# PCB.net
KiCad netlist of a schematic drawn in EasyEDA Pro
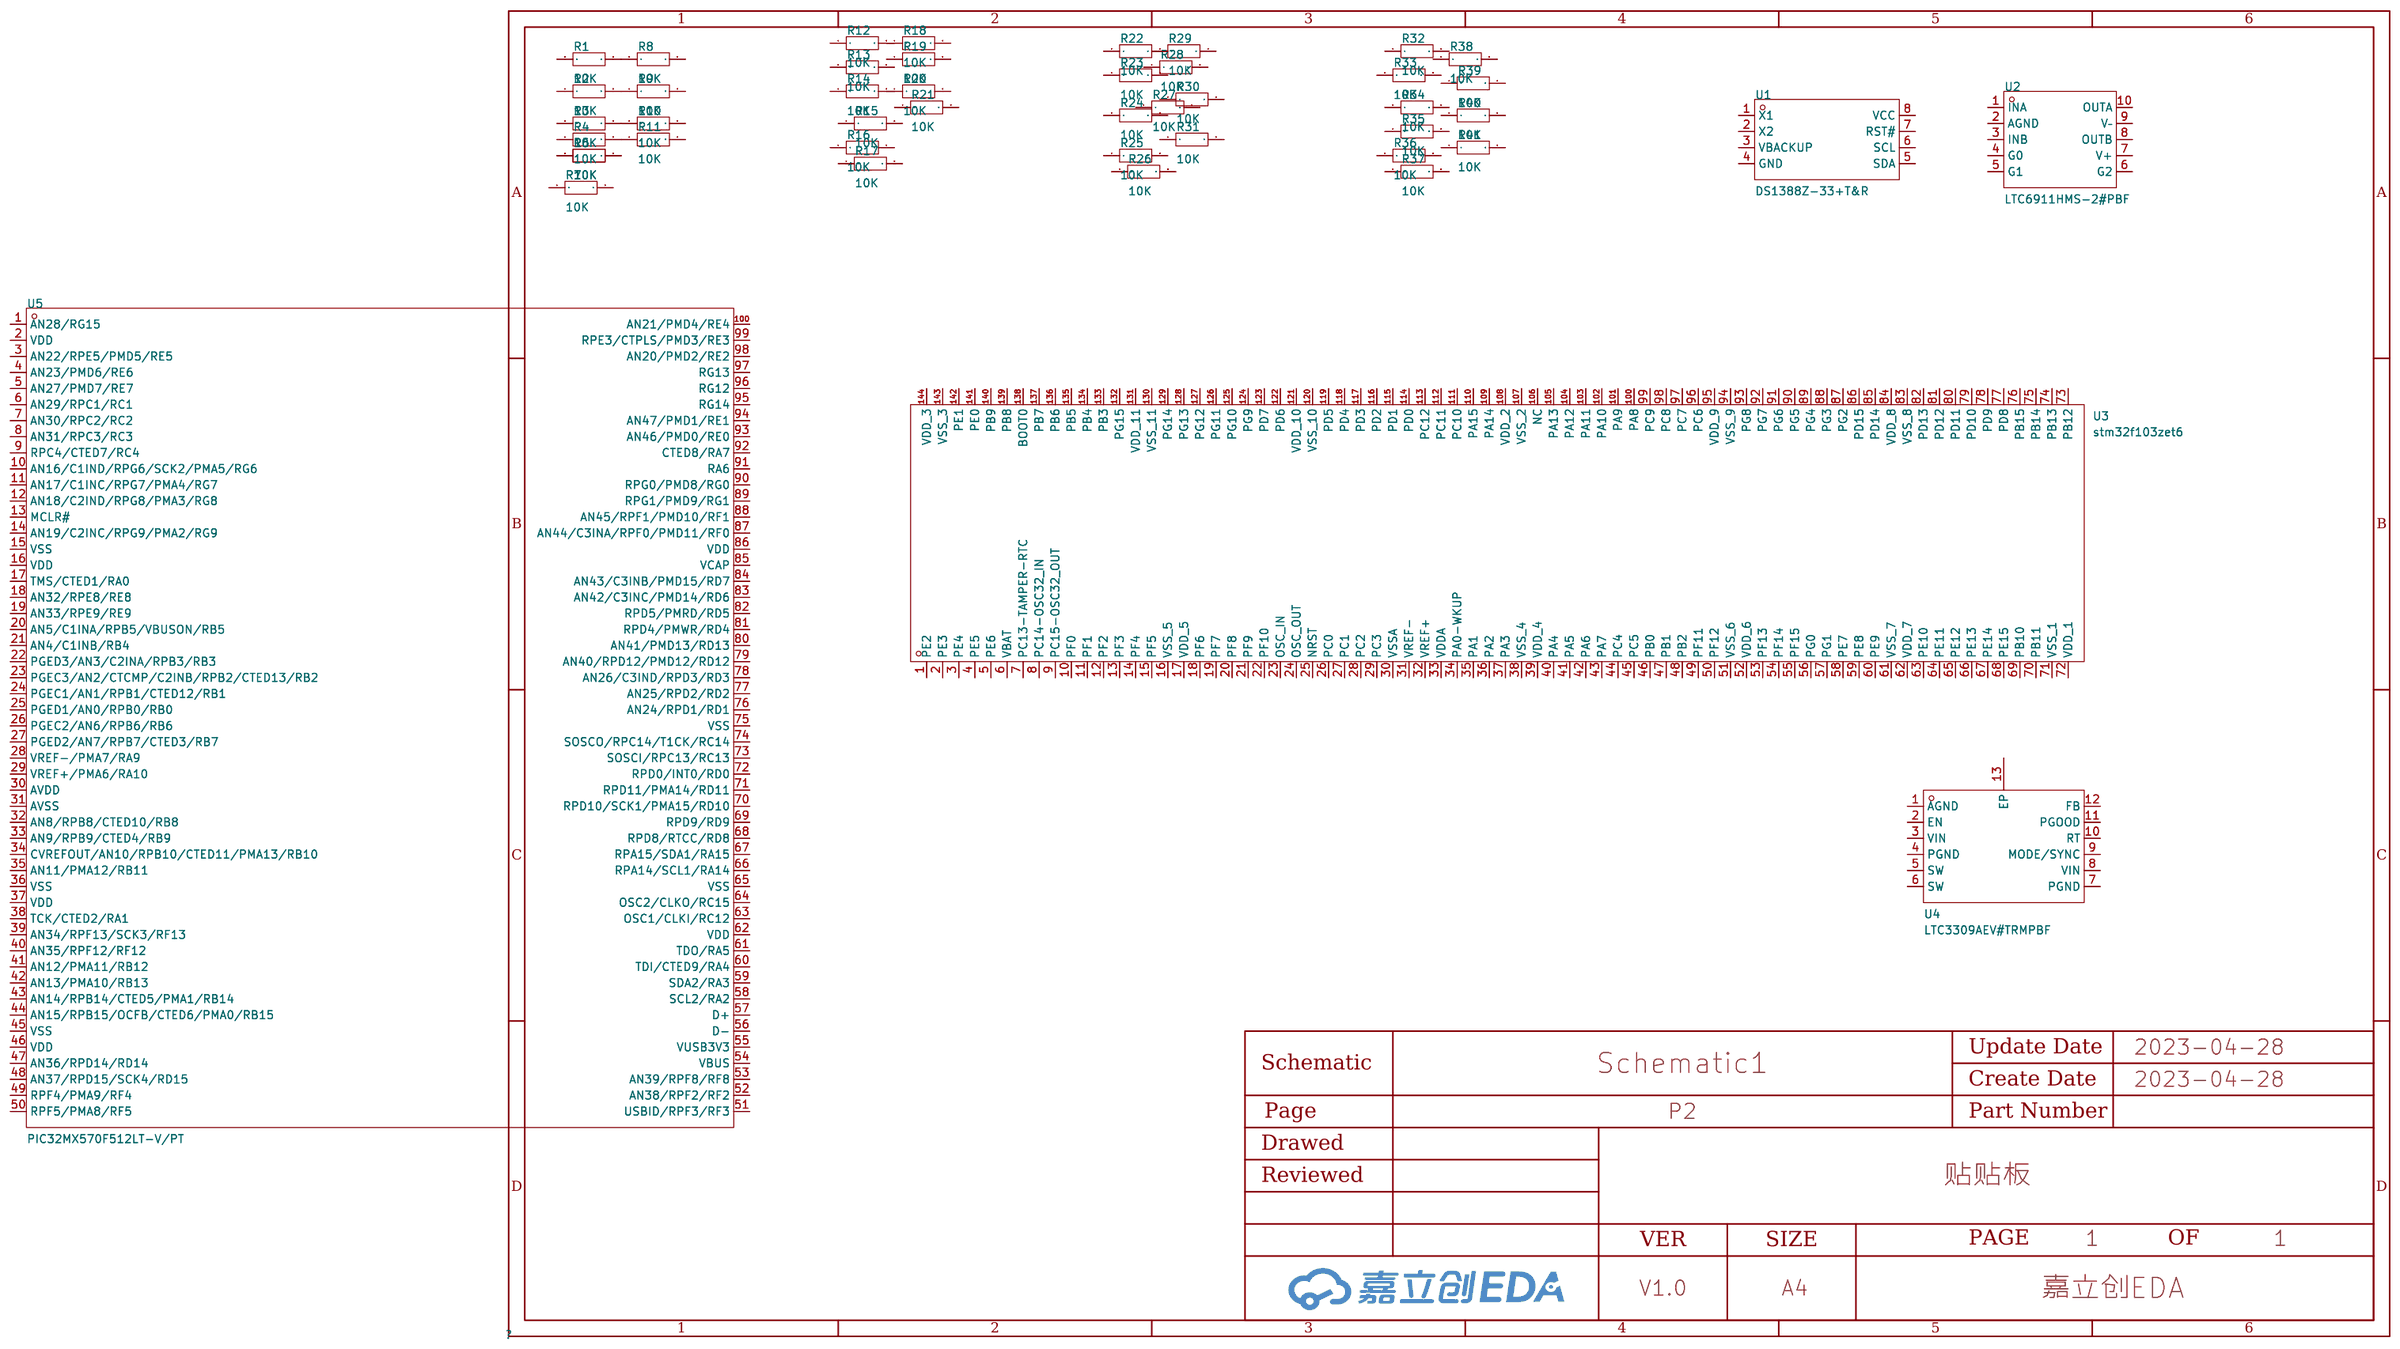
[diagram p0: schematic sheet]

(export (version "E")
  (design (tool "Eeschema 10.0.6"))
  (components
    (comp (ref "R1") (value "10K") (footprint "easyedapro:R1206") (libsource (lib "easyedapro") (part "电阻")))
    (comp (ref "R2") (value "10K") (footprint "easyedapro:R1206") (libsource (lib "easyedapro") (part "电阻")))
    (comp (ref "R3") (value "10K") (footprint "easyedapro:R1206") (libsource (lib "easyedapro") (part "电阻")))
    (comp (ref "R4") (value "10K") (footprint "easyedapro:R1206") (libsource (lib "easyedapro") (part "电阻")))
    (comp (ref "R5") (value "10K") (footprint "easyedapro:R1206") (libsource (lib "easyedapro") (part "电阻")))
    (comp (ref "R6") (value "10K") (footprint "easyedapro:R1206") (libsource (lib "easyedapro") (part "电阻")))
    (comp (ref "R7") (value "10K") (footprint "easyedapro:R1206") (libsource (lib "easyedapro") (part "电阻")))
    (comp (ref "R8") (value "10K") (footprint "easyedapro:R1206") (libsource (lib "easyedapro") (part "电阻")))
    (comp (ref "R9") (value "10K") (footprint "easyedapro:R1206") (libsource (lib "easyedapro") (part "电阻")))
    (comp (ref "R10") (value "10K") (footprint "easyedapro:R1206") (libsource (lib "easyedapro") (part "电阻")))
    (comp (ref "R11") (value "10K") (footprint "easyedapro:R1206") (libsource (lib "easyedapro") (part "电阻")))
    (comp (ref "R12") (value "10K") (footprint "easyedapro:R1206") (libsource (lib "easyedapro") (part "电阻")))
    (comp (ref "R13") (value "10K") (footprint "easyedapro:R1206") (libsource (lib "easyedapro") (part "电阻")))
    (comp (ref "R14") (value "10K") (footprint "easyedapro:R1206") (libsource (lib "easyedapro") (part "电阻")))
    (comp (ref "R15") (value "10K") (footprint "easyedapro:R1206") (libsource (lib "easyedapro") (part "电阻")))
    (comp (ref "R16") (value "10K") (footprint "easyedapro:R1206") (libsource (lib "easyedapro") (part "电阻")))
    (comp (ref "R17") (value "10K") (footprint "easyedapro:R1206") (libsource (lib "easyedapro") (part "电阻")))
    (comp (ref "R18") (value "10K") (footprint "easyedapro:R1206") (libsource (lib "easyedapro") (part "电阻")))
    (comp (ref "R19") (value "10K") (footprint "easyedapro:R1206") (libsource (lib "easyedapro") (part "电阻")))
    (comp (ref "R20") (value "10K") (footprint "easyedapro:R1206") (libsource (lib "easyedapro") (part "电阻")))
    (comp (ref "R21") (value "10K") (footprint "easyedapro:R1206") (libsource (lib "easyedapro") (part "电阻")))
    (comp (ref "R22") (value "10K") (footprint "easyedapro:R1206") (libsource (lib "easyedapro") (part "电阻")))
    (comp (ref "R23") (value "10K") (footprint "easyedapro:R1206") (libsource (lib "easyedapro") (part "电阻")))
    (comp (ref "R24") (value "10K") (footprint "easyedapro:R1206") (libsource (lib "easyedapro") (part "电阻")))
    (comp (ref "R25") (value "10K") (footprint "easyedapro:R1206") (libsource (lib "easyedapro") (part "电阻")))
    (comp (ref "R26") (value "10K") (footprint "easyedapro:R1206") (libsource (lib "easyedapro") (part "电阻")))
    (comp (ref "R27") (value "10K") (footprint "easyedapro:R1206") (libsource (lib "easyedapro") (part "电阻")))
    (comp (ref "R28") (value "10K") (footprint "easyedapro:R1206") (libsource (lib "easyedapro") (part "电阻")))
    (comp (ref "R29") (value "10K") (footprint "easyedapro:R1206") (libsource (lib "easyedapro") (part "电阻")))
    (comp (ref "R30") (value "10K") (footprint "easyedapro:R1206") (libsource (lib "easyedapro") (part "电阻")))
    (comp (ref "R31") (value "10K") (footprint "easyedapro:R1206") (libsource (lib "easyedapro") (part "电阻")))
    (comp (ref "R32") (value "10K") (footprint "easyedapro:R1206") (libsource (lib "easyedapro") (part "电阻")))
    (comp (ref "R33") (value "10K") (footprint "easyedapro:R1206") (libsource (lib "easyedapro") (part "电阻")))
    (comp (ref "R34") (value "10K") (footprint "easyedapro:R1206") (libsource (lib "easyedapro") (part "电阻")))
    (comp (ref "R35") (value "10K") (footprint "easyedapro:R1206") (libsource (lib "easyedapro") (part "电阻")))
    (comp (ref "R36") (value "10K") (footprint "easyedapro:R1206") (libsource (lib "easyedapro") (part "电阻")))
    (comp (ref "R37") (value "10K") (footprint "easyedapro:R1206") (libsource (lib "easyedapro") (part "电阻")))
    (comp (ref "R38") (value "10K") (footprint "easyedapro:R1206") (libsource (lib "easyedapro") (part "电阻")))
    (comp (ref "R39") (value "10K") (footprint "easyedapro:R1206") (libsource (lib "easyedapro") (part "电阻")))
    (comp (ref "R40") (value "10K") (footprint "easyedapro:R1206") (libsource (lib "easyedapro") (part "电阻")))
    (comp (ref "R41") (value "10K") (footprint "easyedapro:R1206") (libsource (lib "easyedapro") (part "电阻")))
    (comp (ref "U1")
      (value "DS1388Z-33+T&R")
      (footprint "easyedapro:SOIC-8_L4.9-W3.9-P1.27-LS6.0-BL")
      (description "接口:I2C;")
      (fields (field (name "Manufacturer") "ADI(亚德诺)/MAXIM(美信)"))
      (libsource (lib "easyedapro") (part "DS1388Z-33+T&R"))
    )
    (comp (ref "U2")
      (value "LTC6911HMS-2#PBF")
      (footprint "easyedapro:MSOP-10_L3.0-W3.0-P0.50-LS4.9-BL")
      (description "放大器类型:-;通道数:2;-3dB带宽:-;输入偏置电流(Ib):-;压摆率(SR):16V/us;")
      (fields (field (name "Manufacturer") "ADI(亚德诺)"))
      (libsource (lib "easyedapro") (part "LTC6911HMS-2#PBF"))
    )
    (comp (ref "U3")
      (value "stm32f103zet6")
      (footprint "easyedapro:LQFP-144_L20.0-W20.0-P0.50-LS22.0-BL")
      (libsource (lib "easyedapro") (part "STM32F103ZET6_C9900046927"))
    )
    (comp (ref "U4")
      (value "LTC3309AEV#TRMPBF")
      (footprint "easyedapro:LQFN-12_L2.0-W2.0-P0.50-TL-EP0.7")
      (fields (field (name "Manufacturer") "ADI(亚德诺)/LINEAR(凌特)"))
      (libsource (lib "easyedapro") (part "LTC3309AEV#TRMPBF"))
    )
    (comp (ref "U5")
      (value "PIC32MX570F512LT-V/PT")
      (footprint "easyedapro:TQFP-100_L12.0-W12.0-P0.40-LS14.0-BL")
      (fields (field (name "Manufacturer") "MICROCHIP(美国微芯)"))
      (libsource (lib "easyedapro") (part "PIC32MX570F512LT-V/PT"))
    )
  )
  (nets
    (net (code "1") (name "Net-(R1-Pad2)") (class "Default")
      (node (ref "R1") (pin "2") (pinfunction "2_2") (pintype "input"))
      (node (ref "R8") (pin "1") (pinfunction "1_1") (pintype "input"))
    )
    (net (code "2") (name "Net-(R2-Pad2)") (class "Default")
      (node (ref "R2") (pin "2") (pinfunction "2_2") (pintype "input"))
      (node (ref "R9") (pin "1") (pinfunction "1_1") (pintype "input"))
    )
    (net (code "3") (name "Net-(R5-Pad1)") (class "Default")
      (node (ref "R5") (pin "1") (pinfunction "1_1") (pintype "input"))
      (node (ref "R6") (pin "1") (pinfunction "1_1") (pintype "input"))
    )
    (net (code "4") (name "Net-(R5-Pad2)") (class "Default")
      (node (ref "R5") (pin "2") (pinfunction "2_2") (pintype "input"))
      (node (ref "R6") (pin "2") (pinfunction "2_2") (pintype "input"))
    )
    (net (code "5") (name "Net-(R10-Pad1)") (class "Default")
      (node (ref "R10") (pin "1") (pinfunction "1_1") (pintype "input"))
      (node (ref "R3") (pin "2") (pinfunction "2_2") (pintype "input"))
    )
    (net (code "6") (name "Net-(R11-Pad1)") (class "Default")
      (node (ref "R11") (pin "1") (pinfunction "1_1") (pintype "input"))
      (node (ref "R4") (pin "2") (pinfunction "2_2") (pintype "input"))
    )
    (net (code "7") (name "unconnected-(R1-Pad1)") (class "Default")
      (node (ref "R1") (pin "1") (pinfunction "1_1") (pintype "input"))
    )
    (net (code "8") (name "unconnected-(R2-Pad1)") (class "Default")
      (node (ref "R2") (pin "1") (pinfunction "1_1") (pintype "input"))
    )
    (net (code "9") (name "unconnected-(R3-Pad1)") (class "Default")
      (node (ref "R3") (pin "1") (pinfunction "1_1") (pintype "input"))
    )
    (net (code "10") (name "unconnected-(R4-Pad1)") (class "Default")
      (node (ref "R4") (pin "1") (pinfunction "1_1") (pintype "input"))
    )
    (net (code "11") (name "unconnected-(R7-Pad1)") (class "Default")
      (node (ref "R7") (pin "1") (pinfunction "1_1") (pintype "input"))
    )
    (net (code "12") (name "unconnected-(R7-Pad2)") (class "Default")
      (node (ref "R7") (pin "2") (pinfunction "2_2") (pintype "input"))
    )
    (net (code "13") (name "unconnected-(R8-Pad2)") (class "Default")
      (node (ref "R8") (pin "2") (pinfunction "2_2") (pintype "input"))
    )
    (net (code "14") (name "unconnected-(R9-Pad2)") (class "Default")
      (node (ref "R9") (pin "2") (pinfunction "2_2") (pintype "input"))
    )
    (net (code "15") (name "unconnected-(R10-Pad2)") (class "Default")
      (node (ref "R10") (pin "2") (pinfunction "2_2") (pintype "input"))
    )
    (net (code "16") (name "unconnected-(R11-Pad2)") (class "Default")
      (node (ref "R11") (pin "2") (pinfunction "2_2") (pintype "input"))
    )
    (net (code "17") (name "unconnected-(R12-Pad1)") (class "Default")
      (node (ref "R12") (pin "1") (pinfunction "1_1") (pintype "input"))
    )
    (net (code "18") (name "unconnected-(R12-Pad2)") (class "Default")
      (node (ref "R12") (pin "2") (pinfunction "2_2") (pintype "input"))
    )
    (net (code "19") (name "unconnected-(R13-Pad1)") (class "Default")
      (node (ref "R13") (pin "1") (pinfunction "1_1") (pintype "input"))
    )
    (net (code "20") (name "unconnected-(R13-Pad2)") (class "Default")
      (node (ref "R13") (pin "2") (pinfunction "2_2") (pintype "input"))
    )
    (net (code "21") (name "unconnected-(R14-Pad1)") (class "Default")
      (node (ref "R14") (pin "1") (pinfunction "1_1") (pintype "input"))
    )
    (net (code "22") (name "unconnected-(R14-Pad2)") (class "Default")
      (node (ref "R14") (pin "2") (pinfunction "2_2") (pintype "input"))
    )
    (net (code "23") (name "unconnected-(R15-Pad1)") (class "Default")
      (node (ref "R15") (pin "1") (pinfunction "1_1") (pintype "input"))
    )
    (net (code "24") (name "unconnected-(R15-Pad2)") (class "Default")
      (node (ref "R15") (pin "2") (pinfunction "2_2") (pintype "input"))
    )
    (net (code "25") (name "unconnected-(R16-Pad1)") (class "Default")
      (node (ref "R16") (pin "1") (pinfunction "1_1") (pintype "input"))
    )
    (net (code "26") (name "unconnected-(R16-Pad2)") (class "Default")
      (node (ref "R16") (pin "2") (pinfunction "2_2") (pintype "input"))
    )
    (net (code "27") (name "unconnected-(R17-Pad1)") (class "Default")
      (node (ref "R17") (pin "1") (pinfunction "1_1") (pintype "input"))
    )
    (net (code "28") (name "unconnected-(R17-Pad2)") (class "Default")
      (node (ref "R17") (pin "2") (pinfunction "2_2") (pintype "input"))
    )
    (net (code "29") (name "unconnected-(R18-Pad1)") (class "Default")
      (node (ref "R18") (pin "1") (pinfunction "1_1") (pintype "input"))
    )
    (net (code "30") (name "unconnected-(R18-Pad2)") (class "Default")
      (node (ref "R18") (pin "2") (pinfunction "2_2") (pintype "input"))
    )
    (net (code "31") (name "unconnected-(R19-Pad1)") (class "Default")
      (node (ref "R19") (pin "1") (pinfunction "1_1") (pintype "input"))
    )
    (net (code "32") (name "unconnected-(R19-Pad2)") (class "Default")
      (node (ref "R19") (pin "2") (pinfunction "2_2") (pintype "input"))
    )
    (net (code "33") (name "unconnected-(R20-Pad1)") (class "Default")
      (node (ref "R20") (pin "1") (pinfunction "1_1") (pintype "input"))
    )
    (net (code "34") (name "unconnected-(R20-Pad2)") (class "Default")
      (node (ref "R20") (pin "2") (pinfunction "2_2") (pintype "input"))
    )
    (net (code "35") (name "unconnected-(R21-Pad1)") (class "Default")
      (node (ref "R21") (pin "1") (pinfunction "1_1") (pintype "input"))
    )
    (net (code "36") (name "unconnected-(R21-Pad2)") (class "Default")
      (node (ref "R21") (pin "2") (pinfunction "2_2") (pintype "input"))
    )
    (net (code "37") (name "unconnected-(R22-Pad1)") (class "Default")
      (node (ref "R22") (pin "1") (pinfunction "1_1") (pintype "input"))
    )
    (net (code "38") (name "unconnected-(R22-Pad2)") (class "Default")
      (node (ref "R22") (pin "2") (pinfunction "2_2") (pintype "input"))
    )
    (net (code "39") (name "unconnected-(R23-Pad1)") (class "Default")
      (node (ref "R23") (pin "1") (pinfunction "1_1") (pintype "input"))
    )
    (net (code "40") (name "unconnected-(R23-Pad2)") (class "Default")
      (node (ref "R23") (pin "2") (pinfunction "2_2") (pintype "input"))
    )
    (net (code "41") (name "unconnected-(R24-Pad1)") (class "Default")
      (node (ref "R24") (pin "1") (pinfunction "1_1") (pintype "input"))
    )
    (net (code "42") (name "unconnected-(R24-Pad2)") (class "Default")
      (node (ref "R24") (pin "2") (pinfunction "2_2") (pintype "input"))
    )
    (net (code "43") (name "unconnected-(R25-Pad1)") (class "Default")
      (node (ref "R25") (pin "1") (pinfunction "1_1") (pintype "input"))
    )
    (net (code "44") (name "unconnected-(R25-Pad2)") (class "Default")
      (node (ref "R25") (pin "2") (pinfunction "2_2") (pintype "input"))
    )
    (net (code "45") (name "unconnected-(R26-Pad1)") (class "Default")
      (node (ref "R26") (pin "1") (pinfunction "1_1") (pintype "input"))
    )
    (net (code "46") (name "unconnected-(R26-Pad2)") (class "Default")
      (node (ref "R26") (pin "2") (pinfunction "2_2") (pintype "input"))
    )
    (net (code "47") (name "unconnected-(R27-Pad1)") (class "Default")
      (node (ref "R27") (pin "1") (pinfunction "1_1") (pintype "input"))
    )
    (net (code "48") (name "unconnected-(R27-Pad2)") (class "Default")
      (node (ref "R27") (pin "2") (pinfunction "2_2") (pintype "input"))
    )
    (net (code "49") (name "unconnected-(R28-Pad1)") (class "Default")
      (node (ref "R28") (pin "1") (pinfunction "1_1") (pintype "input"))
    )
    (net (code "50") (name "unconnected-(R28-Pad2)") (class "Default")
      (node (ref "R28") (pin "2") (pinfunction "2_2") (pintype "input"))
    )
    (net (code "51") (name "unconnected-(R29-Pad1)") (class "Default")
      (node (ref "R29") (pin "1") (pinfunction "1_1") (pintype "input"))
    )
    (net (code "52") (name "unconnected-(R29-Pad2)") (class "Default")
      (node (ref "R29") (pin "2") (pinfunction "2_2") (pintype "input"))
    )
    (net (code "53") (name "unconnected-(R30-Pad1)") (class "Default")
      (node (ref "R30") (pin "1") (pinfunction "1_1") (pintype "input"))
    )
    (net (code "54") (name "unconnected-(R30-Pad2)") (class "Default")
      (node (ref "R30") (pin "2") (pinfunction "2_2") (pintype "input"))
    )
    (net (code "55") (name "unconnected-(R31-Pad1)") (class "Default")
      (node (ref "R31") (pin "1") (pinfunction "1_1") (pintype "input"))
    )
    (net (code "56") (name "unconnected-(R31-Pad2)") (class "Default")
      (node (ref "R31") (pin "2") (pinfunction "2_2") (pintype "input"))
    )
    (net (code "57") (name "unconnected-(R32-Pad1)") (class "Default")
      (node (ref "R32") (pin "1") (pinfunction "1_1") (pintype "input"))
    )
    (net (code "58") (name "unconnected-(R32-Pad2)") (class "Default")
      (node (ref "R32") (pin "2") (pinfunction "2_2") (pintype "input"))
    )
    (net (code "59") (name "unconnected-(R33-Pad1)") (class "Default")
      (node (ref "R33") (pin "1") (pinfunction "1_1") (pintype "input"))
    )
    (net (code "60") (name "unconnected-(R33-Pad2)") (class "Default")
      (node (ref "R33") (pin "2") (pinfunction "2_2") (pintype "input"))
    )
    (net (code "61") (name "unconnected-(R34-Pad1)") (class "Default")
      (node (ref "R34") (pin "1") (pinfunction "1_1") (pintype "input"))
    )
    (net (code "62") (name "unconnected-(R34-Pad2)") (class "Default")
      (node (ref "R34") (pin "2") (pinfunction "2_2") (pintype "input"))
    )
    (net (code "63") (name "unconnected-(R35-Pad1)") (class "Default")
      (node (ref "R35") (pin "1") (pinfunction "1_1") (pintype "input"))
    )
    (net (code "64") (name "unconnected-(R35-Pad2)") (class "Default")
      (node (ref "R35") (pin "2") (pinfunction "2_2") (pintype "input"))
    )
    (net (code "65") (name "unconnected-(R36-Pad1)") (class "Default")
      (node (ref "R36") (pin "1") (pinfunction "1_1") (pintype "input"))
    )
    (net (code "66") (name "unconnected-(R36-Pad2)") (class "Default")
      (node (ref "R36") (pin "2") (pinfunction "2_2") (pintype "input"))
    )
    (net (code "67") (name "unconnected-(R37-Pad1)") (class "Default")
      (node (ref "R37") (pin "1") (pinfunction "1_1") (pintype "input"))
    )
    (net (code "68") (name "unconnected-(R37-Pad2)") (class "Default")
      (node (ref "R37") (pin "2") (pinfunction "2_2") (pintype "input"))
    )
    (net (code "69") (name "unconnected-(R38-Pad1)") (class "Default")
      (node (ref "R38") (pin "1") (pinfunction "1_1") (pintype "input"))
    )
    (net (code "70") (name "unconnected-(R38-Pad2)") (class "Default")
      (node (ref "R38") (pin "2") (pinfunction "2_2") (pintype "input"))
    )
    (net (code "71") (name "unconnected-(R39-Pad1)") (class "Default")
      (node (ref "R39") (pin "1") (pinfunction "1_1") (pintype "input"))
    )
    (net (code "72") (name "unconnected-(R39-Pad2)") (class "Default")
      (node (ref "R39") (pin "2") (pinfunction "2_2") (pintype "input"))
    )
    (net (code "73") (name "unconnected-(R40-Pad1)") (class "Default")
      (node (ref "R40") (pin "1") (pinfunction "1_1") (pintype "input"))
    )
    (net (code "74") (name "unconnected-(R40-Pad2)") (class "Default")
      (node (ref "R40") (pin "2") (pinfunction "2_2") (pintype "input"))
    )
    (net (code "75") (name "unconnected-(R41-Pad1)") (class "Default")
      (node (ref "R41") (pin "1") (pinfunction "1_1") (pintype "input"))
    )
    (net (code "76") (name "unconnected-(R41-Pad2)") (class "Default")
      (node (ref "R41") (pin "2") (pinfunction "2_2") (pintype "input"))
    )
    (net (code "77") (name "unconnected-(U1-GND-Pad4)") (class "Default")
      (node (ref "U1") (pin "4") (pinfunction "GND_4") (pintype "input"))
    )
    (net (code "78") (name "unconnected-(U1-RST#-Pad7)") (class "Default")
      (node (ref "U1") (pin "7") (pinfunction "RST#_7") (pintype "input"))
    )
    (net (code "79") (name "unconnected-(U1-SCL-Pad6)") (class "Default")
      (node (ref "U1") (pin "6") (pinfunction "SCL_6") (pintype "input"))
    )
    (net (code "80") (name "unconnected-(U1-SDA-Pad5)") (class "Default")
      (node (ref "U1") (pin "5") (pinfunction "SDA_5") (pintype "input"))
    )
    (net (code "81") (name "unconnected-(U1-VBACKUP-Pad3)") (class "Default")
      (node (ref "U1") (pin "3") (pinfunction "VBACKUP_3") (pintype "input"))
    )
    (net (code "82") (name "unconnected-(U1-VCC-Pad8)") (class "Default")
      (node (ref "U1") (pin "8") (pinfunction "VCC_8") (pintype "input"))
    )
    (net (code "83") (name "unconnected-(U1-X1-Pad1)") (class "Default")
      (node (ref "U1") (pin "1") (pinfunction "X1_1") (pintype "input"))
    )
    (net (code "84") (name "unconnected-(U1-X2-Pad2)") (class "Default")
      (node (ref "U1") (pin "2") (pinfunction "X2_2") (pintype "input"))
    )
    (net (code "85") (name "unconnected-(U2-AGND-Pad2)") (class "Default")
      (node (ref "U2") (pin "2") (pinfunction "AGND_2") (pintype "input"))
    )
    (net (code "86") (name "unconnected-(U2-G0-Pad4)") (class "Default")
      (node (ref "U2") (pin "4") (pinfunction "G0_4") (pintype "input"))
    )
    (net (code "87") (name "unconnected-(U2-G1-Pad5)") (class "Default")
      (node (ref "U2") (pin "5") (pinfunction "G1_5") (pintype "input"))
    )
    (net (code "88") (name "unconnected-(U2-G2-Pad6)") (class "Default")
      (node (ref "U2") (pin "6") (pinfunction "G2_6") (pintype "input"))
    )
    (net (code "89") (name "unconnected-(U2-INA-Pad1)") (class "Default")
      (node (ref "U2") (pin "1") (pinfunction "INA_1") (pintype "input"))
    )
    (net (code "90") (name "unconnected-(U2-INB-Pad3)") (class "Default")
      (node (ref "U2") (pin "3") (pinfunction "INB_3") (pintype "input"))
    )
    (net (code "91") (name "unconnected-(U2-OUTA-Pad10)") (class "Default")
      (node (ref "U2") (pin "10") (pinfunction "OUTA_10") (pintype "input"))
    )
    (net (code "92") (name "unconnected-(U2-OUTB-Pad8)") (class "Default")
      (node (ref "U2") (pin "8") (pinfunction "OUTB_8") (pintype "input"))
    )
    (net (code "93") (name "unconnected-(U2-V+-Pad7)") (class "Default")
      (node (ref "U2") (pin "7") (pinfunction "V+_7") (pintype "input"))
    )
    (net (code "94") (name "unconnected-(U2-V–-Pad9)") (class "Default")
      (node (ref "U2") (pin "9") (pinfunction "V–_9") (pintype "input"))
    )
    (net (code "95") (name "unconnected-(U3-BOOT0-Pad138)") (class "Default")
      (node (ref "U3") (pin "138") (pinfunction "BOOT0_138") (pintype "input"))
    )
    (net (code "96") (name "unconnected-(U3-NC-Pad106)") (class "Default")
      (node (ref "U3") (pin "106") (pinfunction "NC_106") (pintype "input"))
    )
    (net (code "97") (name "unconnected-(U3-NRST-Pad25)") (class "Default")
      (node (ref "U3") (pin "25") (pinfunction "NRST_25") (pintype "input"))
    )
    (net (code "98") (name "unconnected-(U3-OSC_IN-Pad23)") (class "Default")
      (node (ref "U3") (pin "23") (pinfunction "OSC_IN_23") (pintype "input"))
    )
    (net (code "99") (name "unconnected-(U3-OSC_OUT-Pad24)") (class "Default")
      (node (ref "U3") (pin "24") (pinfunction "OSC_OUT_24") (pintype "input"))
    )
    (net (code "100") (name "unconnected-(U3-PA0-WKUP-Pad34)") (class "Default")
      (node (ref "U3") (pin "34") (pinfunction "PA0-WKUP_34") (pintype "input"))
    )
    (net (code "101") (name "unconnected-(U3-PA1-Pad35)") (class "Default")
      (node (ref "U3") (pin "35") (pinfunction "PA1_35") (pintype "input"))
    )
    (net (code "102") (name "unconnected-(U3-PA2-Pad36)") (class "Default")
      (node (ref "U3") (pin "36") (pinfunction "PA2_36") (pintype "input"))
    )
    (net (code "103") (name "unconnected-(U3-PA3-Pad37)") (class "Default")
      (node (ref "U3") (pin "37") (pinfunction "PA3_37") (pintype "input"))
    )
    (net (code "104") (name "unconnected-(U3-PA4-Pad40)") (class "Default")
      (node (ref "U3") (pin "40") (pinfunction "PA4_40") (pintype "input"))
    )
    (net (code "105") (name "unconnected-(U3-PA5-Pad41)") (class "Default")
      (node (ref "U3") (pin "41") (pinfunction "PA5_41") (pintype "input"))
    )
    (net (code "106") (name "unconnected-(U3-PA6-Pad42)") (class "Default")
      (node (ref "U3") (pin "42") (pinfunction "PA6_42") (pintype "input"))
    )
    (net (code "107") (name "unconnected-(U3-PA7-Pad43)") (class "Default")
      (node (ref "U3") (pin "43") (pinfunction "PA7_43") (pintype "input"))
    )
    (net (code "108") (name "unconnected-(U3-PA8-Pad100)") (class "Default")
      (node (ref "U3") (pin "100") (pinfunction "PA8_100") (pintype "input"))
    )
    (net (code "109") (name "unconnected-(U3-PA9-Pad101)") (class "Default")
      (node (ref "U3") (pin "101") (pinfunction "PA9_101") (pintype "input"))
    )
    (net (code "110") (name "unconnected-(U3-PA10-Pad102)") (class "Default")
      (node (ref "U3") (pin "102") (pinfunction "PA10_102") (pintype "input"))
    )
    (net (code "111") (name "unconnected-(U3-PA11-Pad103)") (class "Default")
      (node (ref "U3") (pin "103") (pinfunction "PA11_103") (pintype "input"))
    )
    (net (code "112") (name "unconnected-(U3-PA12-Pad104)") (class "Default")
      (node (ref "U3") (pin "104") (pinfunction "PA12_104") (pintype "input"))
    )
    (net (code "113") (name "unconnected-(U3-PA13-Pad105)") (class "Default")
      (node (ref "U3") (pin "105") (pinfunction "PA13_105") (pintype "input"))
    )
    (net (code "114") (name "unconnected-(U3-PA14-Pad109)") (class "Default")
      (node (ref "U3") (pin "109") (pinfunction "PA14_109") (pintype "input"))
    )
    (net (code "115") (name "unconnected-(U3-PA15-Pad110)") (class "Default")
      (node (ref "U3") (pin "110") (pinfunction "PA15_110") (pintype "input"))
    )
    (net (code "116") (name "unconnected-(U3-PB0-Pad46)") (class "Default")
      (node (ref "U3") (pin "46") (pinfunction "PB0_46") (pintype "input"))
    )
    (net (code "117") (name "unconnected-(U3-PB1-Pad47)") (class "Default")
      (node (ref "U3") (pin "47") (pinfunction "PB1_47") (pintype "input"))
    )
    (net (code "118") (name "unconnected-(U3-PB2-Pad48)") (class "Default")
      (node (ref "U3") (pin "48") (pinfunction "PB2_48") (pintype "input"))
    )
    (net (code "119") (name "unconnected-(U3-PB3-Pad133)") (class "Default")
      (node (ref "U3") (pin "133") (pinfunction "PB3_133") (pintype "input"))
    )
    (net (code "120") (name "unconnected-(U3-PB4-Pad134)") (class "Default")
      (node (ref "U3") (pin "134") (pinfunction "PB4_134") (pintype "input"))
    )
    (net (code "121") (name "unconnected-(U3-PB5-Pad135)") (class "Default")
      (node (ref "U3") (pin "135") (pinfunction "PB5_135") (pintype "input"))
    )
    (net (code "122") (name "unconnected-(U3-PB6-Pad136)") (class "Default")
      (node (ref "U3") (pin "136") (pinfunction "PB6_136") (pintype "input"))
    )
    (net (code "123") (name "unconnected-(U3-PB7-Pad137)") (class "Default")
      (node (ref "U3") (pin "137") (pinfunction "PB7_137") (pintype "input"))
    )
    (net (code "124") (name "unconnected-(U3-PB8-Pad139)") (class "Default")
      (node (ref "U3") (pin "139") (pinfunction "PB8_139") (pintype "input"))
    )
    (net (code "125") (name "unconnected-(U3-PB9-Pad140)") (class "Default")
      (node (ref "U3") (pin "140") (pinfunction "PB9_140") (pintype "input"))
    )
    (net (code "126") (name "unconnected-(U3-PB10-Pad69)") (class "Default")
      (node (ref "U3") (pin "69") (pinfunction "PB10_69") (pintype "input"))
    )
    (net (code "127") (name "unconnected-(U3-PB11-Pad70)") (class "Default")
      (node (ref "U3") (pin "70") (pinfunction "PB11_70") (pintype "input"))
    )
    (net (code "128") (name "unconnected-(U3-PB12-Pad73)") (class "Default")
      (node (ref "U3") (pin "73") (pinfunction "PB12_73") (pintype "input"))
    )
    (net (code "129") (name "unconnected-(U3-PB13-Pad74)") (class "Default")
      (node (ref "U3") (pin "74") (pinfunction "PB13_74") (pintype "input"))
    )
    (net (code "130") (name "unconnected-(U3-PB14-Pad75)") (class "Default")
      (node (ref "U3") (pin "75") (pinfunction "PB14_75") (pintype "input"))
    )
    (net (code "131") (name "unconnected-(U3-PB15-Pad76)") (class "Default")
      (node (ref "U3") (pin "76") (pinfunction "PB15_76") (pintype "input"))
    )
    (net (code "132") (name "unconnected-(U3-PC0-Pad26)") (class "Default")
      (node (ref "U3") (pin "26") (pinfunction "PC0_26") (pintype "input"))
    )
    (net (code "133") (name "unconnected-(U3-PC1-Pad27)") (class "Default")
      (node (ref "U3") (pin "27") (pinfunction "PC1_27") (pintype "input"))
    )
    (net (code "134") (name "unconnected-(U3-PC2-Pad28)") (class "Default")
      (node (ref "U3") (pin "28") (pinfunction "PC2_28") (pintype "input"))
    )
    (net (code "135") (name "unconnected-(U3-PC3-Pad29)") (class "Default")
      (node (ref "U3") (pin "29") (pinfunction "PC3_29") (pintype "input"))
    )
    (net (code "136") (name "unconnected-(U3-PC4-Pad44)") (class "Default")
      (node (ref "U3") (pin "44") (pinfunction "PC4_44") (pintype "input"))
    )
    (net (code "137") (name "unconnected-(U3-PC5-Pad45)") (class "Default")
      (node (ref "U3") (pin "45") (pinfunction "PC5_45") (pintype "input"))
    )
    (net (code "138") (name "unconnected-(U3-PC6-Pad96)") (class "Default")
      (node (ref "U3") (pin "96") (pinfunction "PC6_96") (pintype "input"))
    )
    (net (code "139") (name "unconnected-(U3-PC7-Pad97)") (class "Default")
      (node (ref "U3") (pin "97") (pinfunction "PC7_97") (pintype "input"))
    )
    (net (code "140") (name "unconnected-(U3-PC8-Pad98)") (class "Default")
      (node (ref "U3") (pin "98") (pinfunction "PC8_98") (pintype "input"))
    )
    (net (code "141") (name "unconnected-(U3-PC9-Pad99)") (class "Default")
      (node (ref "U3") (pin "99") (pinfunction "PC9_99") (pintype "input"))
    )
    (net (code "142") (name "unconnected-(U3-PC10-Pad111)") (class "Default")
      (node (ref "U3") (pin "111") (pinfunction "PC10_111") (pintype "input"))
    )
    (net (code "143") (name "unconnected-(U3-PC11-Pad112)") (class "Default")
      (node (ref "U3") (pin "112") (pinfunction "PC11_112") (pintype "input"))
    )
    (net (code "144") (name "unconnected-(U3-PC12-Pad113)") (class "Default")
      (node (ref "U3") (pin "113") (pinfunction "PC12_113") (pintype "input"))
    )
    (net (code "145") (name "unconnected-(U3-PC13-TAMPER-RTC-Pad7)") (class "Default")
      (node (ref "U3") (pin "7") (pinfunction "PC13-TAMPER-RTC_7") (pintype "input"))
    )
    (net (code "146") (name "unconnected-(U3-PC14-OSC32_IN-Pad8)") (class "Default")
      (node (ref "U3") (pin "8") (pinfunction "PC14-OSC32_IN_8") (pintype "input"))
    )
    (net (code "147") (name "unconnected-(U3-PC15-OSC32_OUT-Pad9)") (class "Default")
      (node (ref "U3") (pin "9") (pinfunction "PC15-OSC32_OUT_9") (pintype "input"))
    )
    (net (code "148") (name "unconnected-(U3-PD0-Pad114)") (class "Default")
      (node (ref "U3") (pin "114") (pinfunction "PD0_114") (pintype "input"))
    )
    (net (code "149") (name "unconnected-(U3-PD1-Pad115)") (class "Default")
      (node (ref "U3") (pin "115") (pinfunction "PD1_115") (pintype "input"))
    )
    (net (code "150") (name "unconnected-(U3-PD2-Pad116)") (class "Default")
      (node (ref "U3") (pin "116") (pinfunction "PD2_116") (pintype "input"))
    )
    (net (code "151") (name "unconnected-(U3-PD3-Pad117)") (class "Default")
      (node (ref "U3") (pin "117") (pinfunction "PD3_117") (pintype "input"))
    )
    (net (code "152") (name "unconnected-(U3-PD4-Pad118)") (class "Default")
      (node (ref "U3") (pin "118") (pinfunction "PD4_118") (pintype "input"))
    )
    (net (code "153") (name "unconnected-(U3-PD5-Pad119)") (class "Default")
      (node (ref "U3") (pin "119") (pinfunction "PD5_119") (pintype "input"))
    )
    (net (code "154") (name "unconnected-(U3-PD6-Pad122)") (class "Default")
      (node (ref "U3") (pin "122") (pinfunction "PD6_122") (pintype "input"))
    )
    (net (code "155") (name "unconnected-(U3-PD7-Pad123)") (class "Default")
      (node (ref "U3") (pin "123") (pinfunction "PD7_123") (pintype "input"))
    )
    (net (code "156") (name "unconnected-(U3-PD8-Pad77)") (class "Default")
      (node (ref "U3") (pin "77") (pinfunction "PD8_77") (pintype "input"))
    )
    (net (code "157") (name "unconnected-(U3-PD9-Pad78)") (class "Default")
      (node (ref "U3") (pin "78") (pinfunction "PD9_78") (pintype "input"))
    )
    (net (code "158") (name "unconnected-(U3-PD10-Pad79)") (class "Default")
      (node (ref "U3") (pin "79") (pinfunction "PD10_79") (pintype "input"))
    )
    (net (code "159") (name "unconnected-(U3-PD11-Pad80)") (class "Default")
      (node (ref "U3") (pin "80") (pinfunction "PD11_80") (pintype "input"))
    )
    (net (code "160") (name "unconnected-(U3-PD12-Pad81)") (class "Default")
      (node (ref "U3") (pin "81") (pinfunction "PD12_81") (pintype "input"))
    )
    (net (code "161") (name "unconnected-(U3-PD13-Pad82)") (class "Default")
      (node (ref "U3") (pin "82") (pinfunction "PD13_82") (pintype "input"))
    )
    (net (code "162") (name "unconnected-(U3-PD14-Pad85)") (class "Default")
      (node (ref "U3") (pin "85") (pinfunction "PD14_85") (pintype "input"))
    )
    (net (code "163") (name "unconnected-(U3-PD15-Pad86)") (class "Default")
      (node (ref "U3") (pin "86") (pinfunction "PD15_86") (pintype "input"))
    )
    (net (code "164") (name "unconnected-(U3-PE0-Pad141)") (class "Default")
      (node (ref "U3") (pin "141") (pinfunction "PE0_141") (pintype "input"))
    )
    (net (code "165") (name "unconnected-(U3-PE1-Pad142)") (class "Default")
      (node (ref "U3") (pin "142") (pinfunction "PE1_142") (pintype "input"))
    )
    (net (code "166") (name "unconnected-(U3-PE2-Pad1)") (class "Default")
      (node (ref "U3") (pin "1") (pinfunction "PE2_1") (pintype "input"))
    )
    (net (code "167") (name "unconnected-(U3-PE3-Pad2)") (class "Default")
      (node (ref "U3") (pin "2") (pinfunction "PE3_2") (pintype "input"))
    )
    (net (code "168") (name "unconnected-(U3-PE4-Pad3)") (class "Default")
      (node (ref "U3") (pin "3") (pinfunction "PE4_3") (pintype "input"))
    )
    (net (code "169") (name "unconnected-(U3-PE5-Pad4)") (class "Default")
      (node (ref "U3") (pin "4") (pinfunction "PE5_4") (pintype "input"))
    )
    (net (code "170") (name "unconnected-(U3-PE6-Pad5)") (class "Default")
      (node (ref "U3") (pin "5") (pinfunction "PE6_5") (pintype "input"))
    )
    (net (code "171") (name "unconnected-(U3-PE7-Pad58)") (class "Default")
      (node (ref "U3") (pin "58") (pinfunction "PE7_58") (pintype "input"))
    )
    (net (code "172") (name "unconnected-(U3-PE8-Pad59)") (class "Default")
      (node (ref "U3") (pin "59") (pinfunction "PE8_59") (pintype "input"))
    )
    (net (code "173") (name "unconnected-(U3-PE9-Pad60)") (class "Default")
      (node (ref "U3") (pin "60") (pinfunction "PE9_60") (pintype "input"))
    )
    (net (code "174") (name "unconnected-(U3-PE10-Pad63)") (class "Default")
      (node (ref "U3") (pin "63") (pinfunction "PE10_63") (pintype "input"))
    )
    (net (code "175") (name "unconnected-(U3-PE11-Pad64)") (class "Default")
      (node (ref "U3") (pin "64") (pinfunction "PE11_64") (pintype "input"))
    )
    (net (code "176") (name "unconnected-(U3-PE12-Pad65)") (class "Default")
      (node (ref "U3") (pin "65") (pinfunction "PE12_65") (pintype "input"))
    )
    (net (code "177") (name "unconnected-(U3-PE13-Pad66)") (class "Default")
      (node (ref "U3") (pin "66") (pinfunction "PE13_66") (pintype "input"))
    )
    (net (code "178") (name "unconnected-(U3-PE14-Pad67)") (class "Default")
      (node (ref "U3") (pin "67") (pinfunction "PE14_67") (pintype "input"))
    )
    (net (code "179") (name "unconnected-(U3-PE15-Pad68)") (class "Default")
      (node (ref "U3") (pin "68") (pinfunction "PE15_68") (pintype "input"))
    )
    (net (code "180") (name "unconnected-(U3-PF0-Pad10)") (class "Default")
      (node (ref "U3") (pin "10") (pinfunction "PF0_10") (pintype "input"))
    )
    (net (code "181") (name "unconnected-(U3-PF1-Pad11)") (class "Default")
      (node (ref "U3") (pin "11") (pinfunction "PF1_11") (pintype "input"))
    )
    (net (code "182") (name "unconnected-(U3-PF2-Pad12)") (class "Default")
      (node (ref "U3") (pin "12") (pinfunction "PF2_12") (pintype "input"))
    )
    (net (code "183") (name "unconnected-(U3-PF3-Pad13)") (class "Default")
      (node (ref "U3") (pin "13") (pinfunction "PF3_13") (pintype "input"))
    )
    (net (code "184") (name "unconnected-(U3-PF4-Pad14)") (class "Default")
      (node (ref "U3") (pin "14") (pinfunction "PF4_14") (pintype "input"))
    )
    (net (code "185") (name "unconnected-(U3-PF5-Pad15)") (class "Default")
      (node (ref "U3") (pin "15") (pinfunction "PF5_15") (pintype "input"))
    )
    (net (code "186") (name "unconnected-(U3-PF6-Pad18)") (class "Default")
      (node (ref "U3") (pin "18") (pinfunction "PF6_18") (pintype "input"))
    )
    (net (code "187") (name "unconnected-(U3-PF7-Pad19)") (class "Default")
      (node (ref "U3") (pin "19") (pinfunction "PF7_19") (pintype "input"))
    )
    (net (code "188") (name "unconnected-(U3-PF8-Pad20)") (class "Default")
      (node (ref "U3") (pin "20") (pinfunction "PF8_20") (pintype "input"))
    )
    (net (code "189") (name "unconnected-(U3-PF9-Pad21)") (class "Default")
      (node (ref "U3") (pin "21") (pinfunction "PF9_21") (pintype "input"))
    )
    (net (code "190") (name "unconnected-(U3-PF10-Pad22)") (class "Default")
      (node (ref "U3") (pin "22") (pinfunction "PF10_22") (pintype "input"))
    )
    (net (code "191") (name "unconnected-(U3-PF11-Pad49)") (class "Default")
      (node (ref "U3") (pin "49") (pinfunction "PF11_49") (pintype "input"))
    )
    (net (code "192") (name "unconnected-(U3-PF12-Pad50)") (class "Default")
      (node (ref "U3") (pin "50") (pinfunction "PF12_50") (pintype "input"))
    )
    (net (code "193") (name "unconnected-(U3-PF13-Pad53)") (class "Default")
      (node (ref "U3") (pin "53") (pinfunction "PF13_53") (pintype "input"))
    )
    (net (code "194") (name "unconnected-(U3-PF14-Pad54)") (class "Default")
      (node (ref "U3") (pin "54") (pinfunction "PF14_54") (pintype "input"))
    )
    (net (code "195") (name "unconnected-(U3-PF15-Pad55)") (class "Default")
      (node (ref "U3") (pin "55") (pinfunction "PF15_55") (pintype "input"))
    )
    (net (code "196") (name "unconnected-(U3-PG0-Pad56)") (class "Default")
      (node (ref "U3") (pin "56") (pinfunction "PG0_56") (pintype "input"))
    )
    (net (code "197") (name "unconnected-(U3-PG1-Pad57)") (class "Default")
      (node (ref "U3") (pin "57") (pinfunction "PG1_57") (pintype "input"))
    )
    (net (code "198") (name "unconnected-(U3-PG2-Pad87)") (class "Default")
      (node (ref "U3") (pin "87") (pinfunction "PG2_87") (pintype "input"))
    )
    (net (code "199") (name "unconnected-(U3-PG3-Pad88)") (class "Default")
      (node (ref "U3") (pin "88") (pinfunction "PG3_88") (pintype "input"))
    )
    (net (code "200") (name "unconnected-(U3-PG4-Pad89)") (class "Default")
      (node (ref "U3") (pin "89") (pinfunction "PG4_89") (pintype "input"))
    )
    (net (code "201") (name "unconnected-(U3-PG5-Pad90)") (class "Default")
      (node (ref "U3") (pin "90") (pinfunction "PG5_90") (pintype "input"))
    )
    (net (code "202") (name "unconnected-(U3-PG6-Pad91)") (class "Default")
      (node (ref "U3") (pin "91") (pinfunction "PG6_91") (pintype "input"))
    )
    (net (code "203") (name "unconnected-(U3-PG7-Pad92)") (class "Default")
      (node (ref "U3") (pin "92") (pinfunction "PG7_92") (pintype "input"))
    )
    (net (code "204") (name "unconnected-(U3-PG8-Pad93)") (class "Default")
      (node (ref "U3") (pin "93") (pinfunction "PG8_93") (pintype "input"))
    )
    (net (code "205") (name "unconnected-(U3-PG9-Pad124)") (class "Default")
      (node (ref "U3") (pin "124") (pinfunction "PG9_124") (pintype "input"))
    )
    (net (code "206") (name "unconnected-(U3-PG10-Pad125)") (class "Default")
      (node (ref "U3") (pin "125") (pinfunction "PG10_125") (pintype "input"))
    )
    (net (code "207") (name "unconnected-(U3-PG11-Pad126)") (class "Default")
      (node (ref "U3") (pin "126") (pinfunction "PG11_126") (pintype "input"))
    )
    (net (code "208") (name "unconnected-(U3-PG12-Pad127)") (class "Default")
      (node (ref "U3") (pin "127") (pinfunction "PG12_127") (pintype "input"))
    )
    (net (code "209") (name "unconnected-(U3-PG13-Pad128)") (class "Default")
      (node (ref "U3") (pin "128") (pinfunction "PG13_128") (pintype "input"))
    )
    (net (code "210") (name "unconnected-(U3-PG14-Pad129)") (class "Default")
      (node (ref "U3") (pin "129") (pinfunction "PG14_129") (pintype "input"))
    )
    (net (code "211") (name "unconnected-(U3-PG15-Pad132)") (class "Default")
      (node (ref "U3") (pin "132") (pinfunction "PG15_132") (pintype "input"))
    )
    (net (code "212") (name "unconnected-(U3-VBAT-Pad6)") (class "Default")
      (node (ref "U3") (pin "6") (pinfunction "VBAT_6") (pintype "input"))
    )
    (net (code "213") (name "unconnected-(U3-VDDA-Pad33)") (class "Default")
      (node (ref "U3") (pin "33") (pinfunction "VDDA_33") (pintype "input"))
    )
    (net (code "214") (name "unconnected-(U3-VDD_1-Pad72)") (class "Default")
      (node (ref "U3") (pin "72") (pinfunction "VDD_1_72") (pintype "input"))
    )
    (net (code "215") (name "unconnected-(U3-VDD_2-Pad108)") (class "Default")
      (node (ref "U3") (pin "108") (pinfunction "VDD_2_108") (pintype "input"))
    )
    (net (code "216") (name "unconnected-(U3-VDD_3-Pad144)") (class "Default")
      (node (ref "U3") (pin "144") (pinfunction "VDD_3_144") (pintype "input"))
    )
    (net (code "217") (name "unconnected-(U3-VDD_4-Pad39)") (class "Default")
      (node (ref "U3") (pin "39") (pinfunction "VDD_4_39") (pintype "input"))
    )
    (net (code "218") (name "unconnected-(U3-VDD_5-Pad17)") (class "Default")
      (node (ref "U3") (pin "17") (pinfunction "VDD_5_17") (pintype "input"))
    )
    (net (code "219") (name "unconnected-(U3-VDD_6-Pad52)") (class "Default")
      (node (ref "U3") (pin "52") (pinfunction "VDD_6_52") (pintype "input"))
    )
    (net (code "220") (name "unconnected-(U3-VDD_7-Pad62)") (class "Default")
      (node (ref "U3") (pin "62") (pinfunction "VDD_7_62") (pintype "input"))
    )
    (net (code "221") (name "unconnected-(U3-VDD_8-Pad84)") (class "Default")
      (node (ref "U3") (pin "84") (pinfunction "VDD_8_84") (pintype "input"))
    )
    (net (code "222") (name "unconnected-(U3-VDD_9-Pad95)") (class "Default")
      (node (ref "U3") (pin "95") (pinfunction "VDD_9_95") (pintype "input"))
    )
    (net (code "223") (name "unconnected-(U3-VDD_10-Pad121)") (class "Default")
      (node (ref "U3") (pin "121") (pinfunction "VDD_10_121") (pintype "input"))
    )
    (net (code "224") (name "unconnected-(U3-VDD_11-Pad131)") (class "Default")
      (node (ref "U3") (pin "131") (pinfunction "VDD_11_131") (pintype "input"))
    )
    (net (code "225") (name "unconnected-(U3-VREF+-Pad32)") (class "Default")
      (node (ref "U3") (pin "32") (pinfunction "VREF+_32") (pintype "input"))
    )
    (net (code "226") (name "unconnected-(U3-VREF--Pad31)") (class "Default")
      (node (ref "U3") (pin "31") (pinfunction "VREF-_31") (pintype "input"))
    )
    (net (code "227") (name "unconnected-(U3-VSSA-Pad30)") (class "Default")
      (node (ref "U3") (pin "30") (pinfunction "VSSA_30") (pintype "input"))
    )
    (net (code "228") (name "unconnected-(U3-VSS_1-Pad71)") (class "Default")
      (node (ref "U3") (pin "71") (pinfunction "VSS_1_71") (pintype "input"))
    )
    (net (code "229") (name "unconnected-(U3-VSS_2-Pad107)") (class "Default")
      (node (ref "U3") (pin "107") (pinfunction "VSS_2_107") (pintype "input"))
    )
    (net (code "230") (name "unconnected-(U3-VSS_3-Pad143)") (class "Default")
      (node (ref "U3") (pin "143") (pinfunction "VSS_3_143") (pintype "input"))
    )
    (net (code "231") (name "unconnected-(U3-VSS_4-Pad38)") (class "Default")
      (node (ref "U3") (pin "38") (pinfunction "VSS_4_38") (pintype "input"))
    )
    (net (code "232") (name "unconnected-(U3-VSS_5-Pad16)") (class "Default")
      (node (ref "U3") (pin "16") (pinfunction "VSS_5_16") (pintype "input"))
    )
    (net (code "233") (name "unconnected-(U3-VSS_6-Pad51)") (class "Default")
      (node (ref "U3") (pin "51") (pinfunction "VSS_6_51") (pintype "input"))
    )
    (net (code "234") (name "unconnected-(U3-VSS_7-Pad61)") (class "Default")
      (node (ref "U3") (pin "61") (pinfunction "VSS_7_61") (pintype "input"))
    )
    (net (code "235") (name "unconnected-(U3-VSS_8-Pad83)") (class "Default")
      (node (ref "U3") (pin "83") (pinfunction "VSS_8_83") (pintype "input"))
    )
    (net (code "236") (name "unconnected-(U3-VSS_9-Pad94)") (class "Default")
      (node (ref "U3") (pin "94") (pinfunction "VSS_9_94") (pintype "input"))
    )
    (net (code "237") (name "unconnected-(U3-VSS_10-Pad120)") (class "Default")
      (node (ref "U3") (pin "120") (pinfunction "VSS_10_120") (pintype "input"))
    )
    (net (code "238") (name "unconnected-(U3-VSS_11-Pad130)") (class "Default")
      (node (ref "U3") (pin "130") (pinfunction "VSS_11_130") (pintype "input"))
    )
    (net (code "239") (name "unconnected-(U4-AGND-Pad1)") (class "Default")
      (node (ref "U4") (pin "1") (pinfunction "AGND_1") (pintype "input"))
    )
    (net (code "240") (name "unconnected-(U4-EN-Pad2)") (class "Default")
      (node (ref "U4") (pin "2") (pinfunction "EN_2") (pintype "input"))
    )
    (net (code "241") (name "unconnected-(U4-EP-Pad13)") (class "Default")
      (node (ref "U4") (pin "13") (pinfunction "EP_13") (pintype "input"))
    )
    (net (code "242") (name "unconnected-(U4-FB-Pad12)") (class "Default")
      (node (ref "U4") (pin "12") (pinfunction "FB_12") (pintype "input"))
    )
    (net (code "243") (name "unconnected-(U4-MODE{slash}SYNC-Pad9)") (class "Default")
      (node (ref "U4") (pin "9") (pinfunction "MODE/SYNC_9") (pintype "input"))
    )
    (net (code "244") (name "unconnected-(U4-PGND-Pad4)") (class "Default")
      (node (ref "U4") (pin "4") (pinfunction "PGND_4") (pintype "input"))
    )
    (net (code "245") (name "unconnected-(U4-PGND-Pad7)") (class "Default")
      (node (ref "U4") (pin "7") (pinfunction "PGND_7") (pintype "input"))
    )
    (net (code "246") (name "unconnected-(U4-PGOOD-Pad11)") (class "Default")
      (node (ref "U4") (pin "11") (pinfunction "PGOOD_11") (pintype "input"))
    )
    (net (code "247") (name "unconnected-(U4-RT-Pad10)") (class "Default")
      (node (ref "U4") (pin "10") (pinfunction "RT_10") (pintype "input"))
    )
    (net (code "248") (name "unconnected-(U4-SW-Pad5)") (class "Default")
      (node (ref "U4") (pin "5") (pinfunction "SW_5") (pintype "input"))
    )
    (net (code "249") (name "unconnected-(U4-SW-Pad6)") (class "Default")
      (node (ref "U4") (pin "6") (pinfunction "SW_6") (pintype "input"))
    )
    (net (code "250") (name "unconnected-(U4-VIN-Pad3)") (class "Default")
      (node (ref "U4") (pin "3") (pinfunction "VIN_3") (pintype "input"))
    )
    (net (code "251") (name "unconnected-(U4-VIN-Pad8)") (class "Default")
      (node (ref "U4") (pin "8") (pinfunction "VIN_8") (pintype "input"))
    )
    (net (code "252") (name "unconnected-(U5-AN4{slash}C1INB{slash}RB4-Pad21)") (class "Default")
      (node (ref "U5") (pin "21") (pinfunction "AN4/C1INB/RB4_21") (pintype "input"))
    )
    (net (code "253") (name "unconnected-(U5-AN5{slash}C1INA{slash}RPB5{slash}VBUSON{slash}RB5-Pad20)") (class "Default")
      (node (ref "U5") (pin "20") (pinfunction "AN5/C1INA/RPB5/VBUSON/RB5_20") (pintype "input"))
    )
    (net (code "254") (name "unconnected-(U5-AN8{slash}RPB8{slash}CTED10{slash}RB8-Pad32)") (class "Default")
      (node (ref "U5") (pin "32") (pinfunction "AN8/RPB8/CTED10/RB8_32") (pintype "input"))
    )
    (net (code "255") (name "unconnected-(U5-AN9{slash}RPB9{slash}CTED4{slash}RB9-Pad33)") (class "Default")
      (node (ref "U5") (pin "33") (pinfunction "AN9/RPB9/CTED4/RB9_33") (pintype "input"))
    )
    (net (code "256") (name "unconnected-(U5-AN11{slash}PMA12{slash}RB11-Pad35)") (class "Default")
      (node (ref "U5") (pin "35") (pinfunction "AN11/PMA12/RB11_35") (pintype "input"))
    )
    (net (code "257") (name "unconnected-(U5-AN12{slash}PMA11{slash}RB12-Pad41)") (class "Default")
      (node (ref "U5") (pin "41") (pinfunction "AN12/PMA11/RB12_41") (pintype "input"))
    )
    (net (code "258") (name "unconnected-(U5-AN13{slash}PMA10{slash}RB13-Pad42)") (class "Default")
      (node (ref "U5") (pin "42") (pinfunction "AN13/PMA10/RB13_42") (pintype "input"))
    )
    (net (code "259") (name "unconnected-(U5-AN14{slash}RPB14{slash}CTED5{slash}PMA1{slash}RB14-Pad43)") (class "Default")
      (node (ref "U5") (pin "43") (pinfunction "AN14/RPB14/CTED5/PMA1/RB14_43") (pintype "input"))
    )
    (net (code "260") (name "unconnected-(U5-AN15{slash}RPB15{slash}OCFB{slash}CTED6{slash}PMA0{slash}RB15-Pad44)") (class "Default")
      (node (ref "U5") (pin "44") (pinfunction "AN15/RPB15/OCFB/CTED6/PMA0/RB15_44") (pintype "input"))
    )
    (net (code "261") (name "unconnected-(U5-AN16{slash}C1IND{slash}RPG6{slash}SCK2{slash}PMA5{slash}RG6-Pad10)") (class "Default")
      (node (ref "U5") (pin "10") (pinfunction "AN16/C1IND/RPG6/SCK2/PMA5/RG6_10") (pintype "input"))
    )
    (net (code "262") (name "unconnected-(U5-AN17{slash}C1INC{slash}RPG7{slash}PMA4{slash}RG7-Pad11)") (class "Default")
      (node (ref "U5") (pin "11") (pinfunction "AN17/C1INC/RPG7/PMA4/RG7_11") (pintype "input"))
    )
    (net (code "263") (name "unconnected-(U5-AN18{slash}C2IND{slash}RPG8{slash}PMA3{slash}RG8-Pad12)") (class "Default")
      (node (ref "U5") (pin "12") (pinfunction "AN18/C2IND/RPG8/PMA3/RG8_12") (pintype "input"))
    )
    (net (code "264") (name "unconnected-(U5-AN19{slash}C2INC{slash}RPG9{slash}PMA2{slash}RG9-Pad14)") (class "Default")
      (node (ref "U5") (pin "14") (pinfunction "AN19/C2INC/RPG9/PMA2/RG9_14") (pintype "input"))
    )
    (net (code "265") (name "unconnected-(U5-AN20{slash}PMD2{slash}RE2-Pad98)") (class "Default")
      (node (ref "U5") (pin "98") (pinfunction "AN20/PMD2/RE2_98") (pintype "input"))
    )
    (net (code "266") (name "unconnected-(U5-AN21{slash}PMD4{slash}RE4-Pad100)") (class "Default")
      (node (ref "U5") (pin "100") (pinfunction "AN21/PMD4/RE4_100") (pintype "input"))
    )
    (net (code "267") (name "unconnected-(U5-AN22{slash}RPE5{slash}PMD5{slash}RE5-Pad3)") (class "Default")
      (node (ref "U5") (pin "3") (pinfunction "AN22/RPE5/PMD5/RE5_3") (pintype "input"))
    )
    (net (code "268") (name "unconnected-(U5-AN23{slash}PMD6{slash}RE6-Pad4)") (class "Default")
      (node (ref "U5") (pin "4") (pinfunction "AN23/PMD6/RE6_4") (pintype "input"))
    )
    (net (code "269") (name "unconnected-(U5-AN24{slash}RPD1{slash}RD1-Pad76)") (class "Default")
      (node (ref "U5") (pin "76") (pinfunction "AN24/RPD1/RD1_76") (pintype "input"))
    )
    (net (code "270") (name "unconnected-(U5-AN25{slash}RPD2{slash}RD2-Pad77)") (class "Default")
      (node (ref "U5") (pin "77") (pinfunction "AN25/RPD2/RD2_77") (pintype "input"))
    )
    (net (code "271") (name "unconnected-(U5-AN26{slash}C3IND{slash}RPD3{slash}RD3-Pad78)") (class "Default")
      (node (ref "U5") (pin "78") (pinfunction "AN26/C3IND/RPD3/RD3_78") (pintype "input"))
    )
    (net (code "272") (name "unconnected-(U5-AN27{slash}PMD7{slash}RE7-Pad5)") (class "Default")
      (node (ref "U5") (pin "5") (pinfunction "AN27/PMD7/RE7_5") (pintype "input"))
    )
    (net (code "273") (name "unconnected-(U5-AN28{slash}RG15-Pad1)") (class "Default")
      (node (ref "U5") (pin "1") (pinfunction "AN28/RG15_1") (pintype "input"))
    )
    (net (code "274") (name "unconnected-(U5-AN29{slash}RPC1{slash}RC1-Pad6)") (class "Default")
      (node (ref "U5") (pin "6") (pinfunction "AN29/RPC1/RC1_6") (pintype "input"))
    )
    (net (code "275") (name "unconnected-(U5-AN30{slash}RPC2{slash}RC2-Pad7)") (class "Default")
      (node (ref "U5") (pin "7") (pinfunction "AN30/RPC2/RC2_7") (pintype "input"))
    )
    (net (code "276") (name "unconnected-(U5-AN31{slash}RPC3{slash}RC3-Pad8)") (class "Default")
      (node (ref "U5") (pin "8") (pinfunction "AN31/RPC3/RC3_8") (pintype "input"))
    )
    (net (code "277") (name "unconnected-(U5-AN32{slash}RPE8{slash}RE8-Pad18)") (class "Default")
      (node (ref "U5") (pin "18") (pinfunction "AN32/RPE8/RE8_18") (pintype "input"))
    )
    (net (code "278") (name "unconnected-(U5-AN33{slash}RPE9{slash}RE9-Pad19)") (class "Default")
      (node (ref "U5") (pin "19") (pinfunction "AN33/RPE9/RE9_19") (pintype "input"))
    )
    (net (code "279") (name "unconnected-(U5-AN34{slash}RPF13{slash}SCK3{slash}RF13-Pad39)") (class "Default")
      (node (ref "U5") (pin "39") (pinfunction "AN34/RPF13/SCK3/RF13_39") (pintype "input"))
    )
    (net (code "280") (name "unconnected-(U5-AN35{slash}RPF12{slash}RF12-Pad40)") (class "Default")
      (node (ref "U5") (pin "40") (pinfunction "AN35/RPF12/RF12_40") (pintype "input"))
    )
    (net (code "281") (name "unconnected-(U5-AN36{slash}RPD14{slash}RD14-Pad47)") (class "Default")
      (node (ref "U5") (pin "47") (pinfunction "AN36/RPD14/RD14_47") (pintype "input"))
    )
    (net (code "282") (name "unconnected-(U5-AN37{slash}RPD15{slash}SCK4{slash}RD15-Pad48)") (class "Default")
      (node (ref "U5") (pin "48") (pinfunction "AN37/RPD15/SCK4/RD15_48") (pintype "input"))
    )
    (net (code "283") (name "unconnected-(U5-AN38{slash}RPF2{slash}RF2-Pad52)") (class "Default")
      (node (ref "U5") (pin "52") (pinfunction "AN38/RPF2/RF2_52") (pintype "input"))
    )
    (net (code "284") (name "unconnected-(U5-AN39{slash}RPF8{slash}RF8-Pad53)") (class "Default")
      (node (ref "U5") (pin "53") (pinfunction "AN39/RPF8/RF8_53") (pintype "input"))
    )
    (net (code "285") (name "unconnected-(U5-AN40{slash}RPD12{slash}PMD12{slash}RD12-Pad79)") (class "Default")
      (node (ref "U5") (pin "79") (pinfunction "AN40/RPD12/PMD12/RD12_79") (pintype "input"))
    )
    (net (code "286") (name "unconnected-(U5-AN41{slash}PMD13{slash}RD13-Pad80)") (class "Default")
      (node (ref "U5") (pin "80") (pinfunction "AN41/PMD13/RD13_80") (pintype "input"))
    )
    (net (code "287") (name "unconnected-(U5-AN42{slash}C3INC{slash}PMD14{slash}RD6-Pad83)") (class "Default")
      (node (ref "U5") (pin "83") (pinfunction "AN42/C3INC/PMD14/RD6_83") (pintype "input"))
    )
    (net (code "288") (name "unconnected-(U5-AN43{slash}C3INB{slash}PMD15{slash}RD7-Pad84)") (class "Default")
      (node (ref "U5") (pin "84") (pinfunction "AN43/C3INB/PMD15/RD7_84") (pintype "input"))
    )
    (net (code "289") (name "unconnected-(U5-AN44{slash}C3INA{slash}RPF0{slash}PMD11{slash}RF0-Pad87)") (class "Default")
      (node (ref "U5") (pin "87") (pinfunction "AN44/C3INA/RPF0/PMD11/RF0_87") (pintype "input"))
    )
    (net (code "290") (name "unconnected-(U5-AN45{slash}RPF1{slash}PMD10{slash}RF1-Pad88)") (class "Default")
      (node (ref "U5") (pin "88") (pinfunction "AN45/RPF1/PMD10/RF1_88") (pintype "input"))
    )
    (net (code "291") (name "unconnected-(U5-AN46{slash}PMD0{slash}RE0-Pad93)") (class "Default")
      (node (ref "U5") (pin "93") (pinfunction "AN46/PMD0/RE0_93") (pintype "input"))
    )
    (net (code "292") (name "unconnected-(U5-AN47{slash}PMD1{slash}RE1-Pad94)") (class "Default")
      (node (ref "U5") (pin "94") (pinfunction "AN47/PMD1/RE1_94") (pintype "input"))
    )
    (net (code "293") (name "unconnected-(U5-AVDD-Pad30)") (class "Default")
      (node (ref "U5") (pin "30") (pinfunction "AVDD_30") (pintype "input"))
    )
    (net (code "294") (name "unconnected-(U5-AVSS-Pad31)") (class "Default")
      (node (ref "U5") (pin "31") (pinfunction "AVSS_31") (pintype "input"))
    )
    (net (code "295") (name "unconnected-(U5-CTED8{slash}RA7-Pad92)") (class "Default")
      (node (ref "U5") (pin "92") (pinfunction "CTED8/RA7_92") (pintype "input"))
    )
    (net (code "296") (name "unconnected-(U5-CVREFOUT{slash}AN10{slash}RPB10{slash}CTED11{slash}PMA13{slash}RB10-Pad34)") (class "Default")
      (node (ref "U5") (pin "34") (pinfunction "CVREFOUT/AN10/RPB10/CTED11/PMA13/RB10_34") (pintype "input"))
    )
    (net (code "297") (name "unconnected-(U5-D+-Pad57)") (class "Default")
      (node (ref "U5") (pin "57") (pinfunction "D+_57") (pintype "input"))
    )
    (net (code "298") (name "unconnected-(U5-D--Pad56)") (class "Default")
      (node (ref "U5") (pin "56") (pinfunction "D-_56") (pintype "input"))
    )
    (net (code "299") (name "unconnected-(U5-MCLR#-Pad13)") (class "Default")
      (node (ref "U5") (pin "13") (pinfunction "MCLR#_13") (pintype "input"))
    )
    (net (code "300") (name "unconnected-(U5-OSC1{slash}CLKI{slash}RC12-Pad63)") (class "Default")
      (node (ref "U5") (pin "63") (pinfunction "OSC1/CLKI/RC12_63") (pintype "input"))
    )
    (net (code "301") (name "unconnected-(U5-OSC2{slash}CLKO{slash}RC15-Pad64)") (class "Default")
      (node (ref "U5") (pin "64") (pinfunction "OSC2/CLKO/RC15_64") (pintype "input"))
    )
    (net (code "302") (name "unconnected-(U5-PGEC1{slash}AN1{slash}RPB1{slash}CTED12{slash}RB1-Pad24)") (class "Default")
      (node (ref "U5") (pin "24") (pinfunction "PGEC1/AN1/RPB1/CTED12/RB1_24") (pintype "input"))
    )
    (net (code "303") (name "unconnected-(U5-PGEC2{slash}AN6{slash}RPB6{slash}RB6-Pad26)") (class "Default")
      (node (ref "U5") (pin "26") (pinfunction "PGEC2/AN6/RPB6/RB6_26") (pintype "input"))
    )
    (net (code "304") (name "unconnected-(U5-PGEC3{slash}AN2{slash}CTCMP{slash}C2INB{slash}RPB2{slash}CTED13{slash}RB2-Pad23)") (class "Default")
      (node (ref "U5") (pin "23") (pinfunction "PGEC3/AN2/CTCMP/C2INB/RPB2/CTED13/RB2_23") (pintype "input"))
    )
    (net (code "305") (name "unconnected-(U5-PGED1{slash}AN0{slash}RPB0{slash}RB0-Pad25)") (class "Default")
      (node (ref "U5") (pin "25") (pinfunction "PGED1/AN0/RPB0/RB0_25") (pintype "input"))
    )
    (net (code "306") (name "unconnected-(U5-PGED2{slash}AN7{slash}RPB7{slash}CTED3{slash}RB7-Pad27)") (class "Default")
      (node (ref "U5") (pin "27") (pinfunction "PGED2/AN7/RPB7/CTED3/RB7_27") (pintype "input"))
    )
    (net (code "307") (name "unconnected-(U5-PGED3{slash}AN3{slash}C2INA{slash}RPB3{slash}RB3-Pad22)") (class "Default")
      (node (ref "U5") (pin "22") (pinfunction "PGED3/AN3/C2INA/RPB3/RB3_22") (pintype "input"))
    )
    (net (code "308") (name "unconnected-(U5-RA6-Pad91)") (class "Default")
      (node (ref "U5") (pin "91") (pinfunction "RA6_91") (pintype "input"))
    )
    (net (code "309") (name "unconnected-(U5-RG12-Pad96)") (class "Default")
      (node (ref "U5") (pin "96") (pinfunction "RG12_96") (pintype "input"))
    )
    (net (code "310") (name "unconnected-(U5-RG13-Pad97)") (class "Default")
      (node (ref "U5") (pin "97") (pinfunction "RG13_97") (pintype "input"))
    )
    (net (code "311") (name "unconnected-(U5-RG14-Pad95)") (class "Default")
      (node (ref "U5") (pin "95") (pinfunction "RG14_95") (pintype "input"))
    )
    (net (code "312") (name "unconnected-(U5-RPA14{slash}SCL1{slash}RA14-Pad66)") (class "Default")
      (node (ref "U5") (pin "66") (pinfunction "RPA14/SCL1/RA14_66") (pintype "input"))
    )
    (net (code "313") (name "unconnected-(U5-RPA15{slash}SDA1{slash}RA15-Pad67)") (class "Default")
      (node (ref "U5") (pin "67") (pinfunction "RPA15/SDA1/RA15_67") (pintype "input"))
    )
    (net (code "314") (name "unconnected-(U5-RPC4{slash}CTED7{slash}RC4-Pad9)") (class "Default")
      (node (ref "U5") (pin "9") (pinfunction "RPC4/CTED7/RC4_9") (pintype "input"))
    )
    (net (code "315") (name "unconnected-(U5-RPD0{slash}INT0{slash}RD0-Pad72)") (class "Default")
      (node (ref "U5") (pin "72") (pinfunction "RPD0/INT0/RD0_72") (pintype "input"))
    )
    (net (code "316") (name "unconnected-(U5-RPD4{slash}PMWR{slash}RD4-Pad81)") (class "Default")
      (node (ref "U5") (pin "81") (pinfunction "RPD4/PMWR/RD4_81") (pintype "input"))
    )
    (net (code "317") (name "unconnected-(U5-RPD5{slash}PMRD{slash}RD5-Pad82)") (class "Default")
      (node (ref "U5") (pin "82") (pinfunction "RPD5/PMRD/RD5_82") (pintype "input"))
    )
    (net (code "318") (name "unconnected-(U5-RPD8{slash}RTCC{slash}RD8-Pad68)") (class "Default")
      (node (ref "U5") (pin "68") (pinfunction "RPD8/RTCC/RD8_68") (pintype "input"))
    )
    (net (code "319") (name "unconnected-(U5-RPD9{slash}RD9-Pad69)") (class "Default")
      (node (ref "U5") (pin "69") (pinfunction "RPD9/RD9_69") (pintype "input"))
    )
    (net (code "320") (name "unconnected-(U5-RPD10{slash}SCK1{slash}PMA15{slash}RD10-Pad70)") (class "Default")
      (node (ref "U5") (pin "70") (pinfunction "RPD10/SCK1/PMA15/RD10_70") (pintype "input"))
    )
    (net (code "321") (name "unconnected-(U5-RPD11{slash}PMA14{slash}RD11-Pad71)") (class "Default")
      (node (ref "U5") (pin "71") (pinfunction "RPD11/PMA14/RD11_71") (pintype "input"))
    )
    (net (code "322") (name "unconnected-(U5-RPE3{slash}CTPLS{slash}PMD3{slash}RE3-Pad99)") (class "Default")
      (node (ref "U5") (pin "99") (pinfunction "RPE3/CTPLS/PMD3/RE3_99") (pintype "input"))
    )
    (net (code "323") (name "unconnected-(U5-RPF4{slash}PMA9{slash}RF4-Pad49)") (class "Default")
      (node (ref "U5") (pin "49") (pinfunction "RPF4/PMA9/RF4_49") (pintype "input"))
    )
    (net (code "324") (name "unconnected-(U5-RPF5{slash}PMA8{slash}RF5-Pad50)") (class "Default")
      (node (ref "U5") (pin "50") (pinfunction "RPF5/PMA8/RF5_50") (pintype "input"))
    )
    (net (code "325") (name "unconnected-(U5-RPG0{slash}PMD8{slash}RG0-Pad90)") (class "Default")
      (node (ref "U5") (pin "90") (pinfunction "RPG0/PMD8/RG0_90") (pintype "input"))
    )
    (net (code "326") (name "unconnected-(U5-RPG1{slash}PMD9{slash}RG1-Pad89)") (class "Default")
      (node (ref "U5") (pin "89") (pinfunction "RPG1/PMD9/RG1_89") (pintype "input"))
    )
    (net (code "327") (name "unconnected-(U5-SCL2{slash}RA2-Pad58)") (class "Default")
      (node (ref "U5") (pin "58") (pinfunction "SCL2/RA2_58") (pintype "input"))
    )
    (net (code "328") (name "unconnected-(U5-SDA2{slash}RA3-Pad59)") (class "Default")
      (node (ref "U5") (pin "59") (pinfunction "SDA2/RA3_59") (pintype "input"))
    )
    (net (code "329") (name "unconnected-(U5-SOSCI{slash}RPC13{slash}RC13-Pad73)") (class "Default")
      (node (ref "U5") (pin "73") (pinfunction "SOSCI/RPC13/RC13_73") (pintype "input"))
    )
    (net (code "330") (name "unconnected-(U5-SOSCO{slash}RPC14{slash}T1CK{slash}RC14-Pad74)") (class "Default")
      (node (ref "U5") (pin "74") (pinfunction "SOSCO/RPC14/T1CK/RC14_74") (pintype "input"))
    )
    (net (code "331") (name "unconnected-(U5-TCK{slash}CTED2{slash}RA1-Pad38)") (class "Default")
      (node (ref "U5") (pin "38") (pinfunction "TCK/CTED2/RA1_38") (pintype "input"))
    )
    (net (code "332") (name "unconnected-(U5-TDI{slash}CTED9{slash}RA4-Pad60)") (class "Default")
      (node (ref "U5") (pin "60") (pinfunction "TDI/CTED9/RA4_60") (pintype "input"))
    )
    (net (code "333") (name "unconnected-(U5-TDO{slash}RA5-Pad61)") (class "Default")
      (node (ref "U5") (pin "61") (pinfunction "TDO/RA5_61") (pintype "input"))
    )
    (net (code "334") (name "unconnected-(U5-TMS{slash}CTED1{slash}RA0-Pad17)") (class "Default")
      (node (ref "U5") (pin "17") (pinfunction "TMS/CTED1/RA0_17") (pintype "input"))
    )
    (net (code "335") (name "unconnected-(U5-USBID{slash}RPF3{slash}RF3-Pad51)") (class "Default")
      (node (ref "U5") (pin "51") (pinfunction "USBID/RPF3/RF3_51") (pintype "input"))
    )
    (net (code "336") (name "unconnected-(U5-VBUS-Pad54)") (class "Default")
      (node (ref "U5") (pin "54") (pinfunction "VBUS_54") (pintype "input"))
    )
    (net (code "337") (name "unconnected-(U5-VCAP-Pad85)") (class "Default")
      (node (ref "U5") (pin "85") (pinfunction "VCAP_85") (pintype "input"))
    )
    (net (code "338") (name "unconnected-(U5-VDD-Pad2)") (class "Default")
      (node (ref "U5") (pin "2") (pinfunction "VDD_2") (pintype "input"))
    )
    (net (code "339") (name "unconnected-(U5-VDD-Pad16)") (class "Default")
      (node (ref "U5") (pin "16") (pinfunction "VDD_16") (pintype "input"))
    )
    (net (code "340") (name "unconnected-(U5-VDD-Pad37)") (class "Default")
      (node (ref "U5") (pin "37") (pinfunction "VDD_37") (pintype "input"))
    )
    (net (code "341") (name "unconnected-(U5-VDD-Pad46)") (class "Default")
      (node (ref "U5") (pin "46") (pinfunction "VDD_46") (pintype "input"))
    )
    (net (code "342") (name "unconnected-(U5-VDD-Pad62)") (class "Default")
      (node (ref "U5") (pin "62") (pinfunction "VDD_62") (pintype "input"))
    )
    (net (code "343") (name "unconnected-(U5-VDD-Pad86)") (class "Default")
      (node (ref "U5") (pin "86") (pinfunction "VDD_86") (pintype "input"))
    )
    (net (code "344") (name "unconnected-(U5-VREF+{slash}PMA6{slash}RA10-Pad29)") (class "Default")
      (node (ref "U5") (pin "29") (pinfunction "VREF+/PMA6/RA10_29") (pintype "input"))
    )
    (net (code "345") (name "unconnected-(U5-VREF-{slash}PMA7{slash}RA9-Pad28)") (class "Default")
      (node (ref "U5") (pin "28") (pinfunction "VREF-/PMA7/RA9_28") (pintype "input"))
    )
    (net (code "346") (name "unconnected-(U5-VSS-Pad15)") (class "Default")
      (node (ref "U5") (pin "15") (pinfunction "VSS_15") (pintype "input"))
    )
    (net (code "347") (name "unconnected-(U5-VSS-Pad36)") (class "Default")
      (node (ref "U5") (pin "36") (pinfunction "VSS_36") (pintype "input"))
    )
    (net (code "348") (name "unconnected-(U5-VSS-Pad45)") (class "Default")
      (node (ref "U5") (pin "45") (pinfunction "VSS_45") (pintype "input"))
    )
    (net (code "349") (name "unconnected-(U5-VSS-Pad65)") (class "Default")
      (node (ref "U5") (pin "65") (pinfunction "VSS_65") (pintype "input"))
    )
    (net (code "350") (name "unconnected-(U5-VSS-Pad75)") (class "Default")
      (node (ref "U5") (pin "75") (pinfunction "VSS_75") (pintype "input"))
    )
    (net (code "351") (name "unconnected-(U5-VUSB3V3-Pad55)") (class "Default")
      (node (ref "U5") (pin "55") (pinfunction "VUSB3V3_55") (pintype "input"))
    )
  )
)
